# 06_Logic_Level_Shifters.net
KiCad netlist of a schematic drawn in Altium Designer
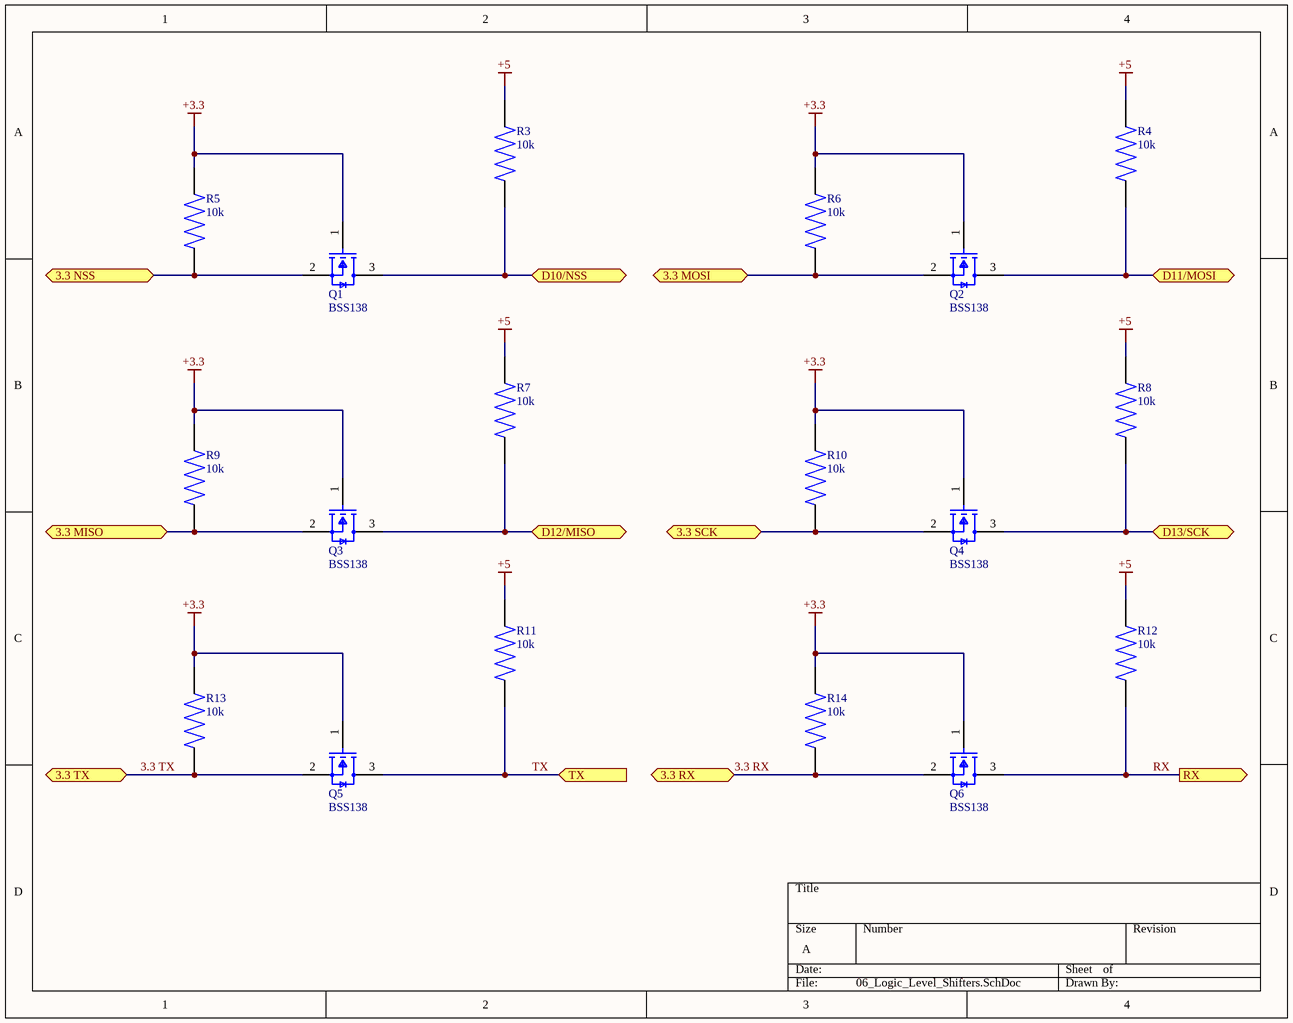
[diagram p0: 06_Logic_Level_Shifters.SchDoc]

(export (version "E")
  (design (tool "Eeschema 10.0.6"))
  (components
    (comp (ref "Q1")
      (value "BSS138")
      (footprint "FP-318-08-IPC_B")
      (description "MOSFET N-CH 50V 220MA SOT-23")
      (libsource (lib "Altium Content Vault") (part "3b9c635fedb024a5347a57b145af9cc"))
    )
    (comp (ref "Q2")
      (value "BSS138")
      (footprint "FP-318-08-IPC_B")
      (description "MOSFET N-CH 50V 220MA SOT-23")
      (libsource (lib "Altium Content Vault") (part "3b9c635fedb024a5347a57b145af9cc"))
    )
    (comp (ref "Q3")
      (value "BSS138")
      (footprint "FP-318-08-IPC_B")
      (description "MOSFET N-CH 50V 220MA SOT-23")
      (libsource (lib "Altium Content Vault") (part "3b9c635fedb024a5347a57b145af9cc"))
    )
    (comp (ref "Q4")
      (value "BSS138")
      (footprint "FP-318-08-IPC_B")
      (description "MOSFET N-CH 50V 220MA SOT-23")
      (libsource (lib "Altium Content Vault") (part "3b9c635fedb024a5347a57b145af9cc"))
    )
    (comp (ref "Q5")
      (value "BSS138")
      (footprint "FP-318-08-IPC_B")
      (description "MOSFET N-CH 50V 220MA SOT-23")
      (libsource (lib "Altium Content Vault") (part "3b9c635fedb024a5347a57b145af9cc"))
    )
    (comp (ref "Q6")
      (value "BSS138")
      (footprint "FP-318-08-IPC_B")
      (description "MOSFET N-CH 50V 220MA SOT-23")
      (libsource (lib "Altium Content Vault") (part "3b9c635fedb024a5347a57b145af9cc"))
    )
    (comp (ref "R3")
      (value "10k")
      (footprint "RESC3115X65N")
      (description "Res Thick Film 1206 4.7K Ohm 1% 0.25W(1/4W) Â±100ppm/C Pad SMD T/R")
      (fields (field (name "MF") "TE Connectivity") (field (name "MP") "CRG1206F4K7/10"))
      (libsource (lib "RFID") (part "CRG1206F4K7/10"))
    )
    (comp (ref "R4")
      (value "10k")
      (footprint "RESC3115X65N")
      (description "Res Thick Film 1206 4.7K Ohm 1% 0.25W(1/4W) Â±100ppm/C Pad SMD T/R")
      (fields (field (name "MF") "TE Connectivity") (field (name "MP") "CRG1206F4K7/10"))
      (libsource (lib "RFID") (part "CRG1206F4K7/10"))
    )
    (comp (ref "R5")
      (value "10k")
      (footprint "RESC3115X65N")
      (description "Res Thick Film 1206 4.7K Ohm 1% 0.25W(1/4W) Â±100ppm/C Pad SMD T/R")
      (fields (field (name "MF") "TE Connectivity") (field (name "MP") "CRG1206F4K7/10"))
      (libsource (lib "RFID") (part "CRG1206F4K7/10"))
    )
    (comp (ref "R6")
      (value "10k")
      (footprint "RESC3115X65N")
      (description "Res Thick Film 1206 4.7K Ohm 1% 0.25W(1/4W) Â±100ppm/C Pad SMD T/R")
      (fields (field (name "MF") "TE Connectivity") (field (name "MP") "CRG1206F4K7/10"))
      (libsource (lib "RFID") (part "CRG1206F4K7/10"))
    )
    (comp (ref "R7")
      (value "10k")
      (footprint "RESC3115X65N")
      (description "Res Thick Film 1206 4.7K Ohm 1% 0.25W(1/4W) Â±100ppm/C Pad SMD T/R")
      (fields (field (name "MF") "TE Connectivity") (field (name "MP") "CRG1206F4K7/10"))
      (libsource (lib "RFID") (part "CRG1206F4K7/10"))
    )
    (comp (ref "R8")
      (value "10k")
      (footprint "RESC3115X65N")
      (description "Res Thick Film 1206 4.7K Ohm 1% 0.25W(1/4W) Â±100ppm/C Pad SMD T/R")
      (fields (field (name "MF") "TE Connectivity") (field (name "MP") "CRG1206F4K7/10"))
      (libsource (lib "RFID") (part "CRG1206F4K7/10"))
    )
    (comp (ref "R9")
      (value "10k")
      (footprint "RESC3115X65N")
      (description "Res Thick Film 1206 4.7K Ohm 1% 0.25W(1/4W) Â±100ppm/C Pad SMD T/R")
      (fields (field (name "MF") "TE Connectivity") (field (name "MP") "CRG1206F4K7/10"))
      (libsource (lib "RFID") (part "CRG1206F4K7/10"))
    )
    (comp (ref "R10")
      (value "10k")
      (footprint "RESC3115X65N")
      (description "Res Thick Film 1206 4.7K Ohm 1% 0.25W(1/4W) Â±100ppm/C Pad SMD T/R")
      (fields (field (name "MF") "TE Connectivity") (field (name "MP") "CRG1206F4K7/10"))
      (libsource (lib "RFID") (part "CRG1206F4K7/10"))
    )
    (comp (ref "R11")
      (value "10k")
      (footprint "RESC3115X65N")
      (description "Res Thick Film 1206 4.7K Ohm 1% 0.25W(1/4W) Â±100ppm/C Pad SMD T/R")
      (fields (field (name "MF") "TE Connectivity") (field (name "MP") "CRG1206F4K7/10"))
      (libsource (lib "RFID") (part "CRG1206F4K7/10"))
    )
    (comp (ref "R12")
      (value "10k")
      (footprint "RESC3115X65N")
      (description "Res Thick Film 1206 4.7K Ohm 1% 0.25W(1/4W) Â±100ppm/C Pad SMD T/R")
      (fields (field (name "MF") "TE Connectivity") (field (name "MP") "CRG1206F4K7/10"))
      (libsource (lib "RFID") (part "CRG1206F4K7/10"))
    )
    (comp (ref "R13")
      (value "10k")
      (footprint "RESC3115X65N")
      (description "Res Thick Film 1206 4.7K Ohm 1% 0.25W(1/4W) Â±100ppm/C Pad SMD T/R")
      (fields (field (name "MF") "TE Connectivity") (field (name "MP") "CRG1206F4K7/10"))
      (libsource (lib "RFID") (part "CRG1206F4K7/10"))
    )
    (comp (ref "R14")
      (value "10k")
      (footprint "RESC3115X65N")
      (description "Res Thick Film 1206 4.7K Ohm 1% 0.25W(1/4W) Â±100ppm/C Pad SMD T/R")
      (fields (field (name "MF") "TE Connectivity") (field (name "MP") "CRG1206F4K7/10"))
      (libsource (lib "RFID") (part "CRG1206F4K7/10"))
    )
  )
  (nets
    (net (code "1") (name "+3.3") (class "Default")
      (node (ref "Q1") (pin "1") (pinfunction "G_1") (pintype "passive"))
      (node (ref "Q2") (pin "1") (pinfunction "G_1") (pintype "passive"))
      (node (ref "Q3") (pin "1") (pinfunction "G_1") (pintype "passive"))
      (node (ref "Q4") (pin "1") (pinfunction "G_1") (pintype "passive"))
      (node (ref "Q5") (pin "1") (pinfunction "G_1") (pintype "passive"))
      (node (ref "Q6") (pin "1") (pinfunction "G_1") (pintype "passive"))
      (node (ref "R10") (pin "2") (pinfunction "2_2") (pintype "passive"))
      (node (ref "R13") (pin "2") (pinfunction "2_2") (pintype "passive"))
      (node (ref "R14") (pin "2") (pinfunction "2_2") (pintype "passive"))
      (node (ref "R5") (pin "2") (pinfunction "2_2") (pintype "passive"))
      (node (ref "R6") (pin "2") (pinfunction "2_2") (pintype "passive"))
      (node (ref "R9") (pin "2") (pinfunction "2_2") (pintype "passive"))
    )
    (net (code "2") (name "+5") (class "Default")
      (node (ref "R11") (pin "2") (pinfunction "2_2") (pintype "passive"))
      (node (ref "R12") (pin "2") (pinfunction "2_2") (pintype "passive"))
      (node (ref "R3") (pin "2") (pinfunction "2_2") (pintype "passive"))
      (node (ref "R4") (pin "2") (pinfunction "2_2") (pintype "passive"))
      (node (ref "R7") (pin "2") (pinfunction "2_2") (pintype "passive"))
      (node (ref "R8") (pin "2") (pinfunction "2_2") (pintype "passive"))
    )
    (net (code "3") (name "/3.3 MISO") (class "Default")
      (node (ref "Q3") (pin "2") (pinfunction "S_2") (pintype "passive"))
      (node (ref "R9") (pin "1") (pinfunction "1_1") (pintype "passive"))
    )
    (net (code "4") (name "/3.3 MOSI") (class "Default")
      (node (ref "Q2") (pin "2") (pinfunction "S_2") (pintype "passive"))
      (node (ref "R6") (pin "1") (pinfunction "1_1") (pintype "passive"))
    )
    (net (code "5") (name "/3.3 NSS") (class "Default")
      (node (ref "Q1") (pin "2") (pinfunction "S_2") (pintype "passive"))
      (node (ref "R5") (pin "1") (pinfunction "1_1") (pintype "passive"))
    )
    (net (code "6") (name "/3.3 RX") (class "Default")
      (node (ref "Q6") (pin "2") (pinfunction "S_2") (pintype "passive"))
      (node (ref "R14") (pin "1") (pinfunction "1_1") (pintype "passive"))
    )
    (net (code "7") (name "/3.3 SCK") (class "Default")
      (node (ref "Q4") (pin "2") (pinfunction "S_2") (pintype "passive"))
      (node (ref "R10") (pin "1") (pinfunction "1_1") (pintype "passive"))
    )
    (net (code "8") (name "/3.3 TX") (class "Default")
      (node (ref "Q5") (pin "2") (pinfunction "S_2") (pintype "passive"))
      (node (ref "R13") (pin "1") (pinfunction "1_1") (pintype "passive"))
    )
    (net (code "9") (name "/D10{slash}NSS") (class "Default")
      (node (ref "Q1") (pin "3") (pinfunction "D_3") (pintype "passive"))
      (node (ref "R3") (pin "1") (pinfunction "1_1") (pintype "passive"))
    )
    (net (code "10") (name "/D11{slash}MOSI") (class "Default")
      (node (ref "Q2") (pin "3") (pinfunction "D_3") (pintype "passive"))
      (node (ref "R4") (pin "1") (pinfunction "1_1") (pintype "passive"))
    )
    (net (code "11") (name "/D12{slash}MISO") (class "Default")
      (node (ref "Q3") (pin "3") (pinfunction "D_3") (pintype "passive"))
      (node (ref "R7") (pin "1") (pinfunction "1_1") (pintype "passive"))
    )
    (net (code "12") (name "/D13{slash}SCK") (class "Default")
      (node (ref "Q4") (pin "3") (pinfunction "D_3") (pintype "passive"))
      (node (ref "R8") (pin "1") (pinfunction "1_1") (pintype "passive"))
    )
    (net (code "13") (name "/RX") (class "Default")
      (node (ref "Q6") (pin "3") (pinfunction "D_3") (pintype "passive"))
      (node (ref "R12") (pin "1") (pinfunction "1_1") (pintype "passive"))
    )
    (net (code "14") (name "/TX") (class "Default")
      (node (ref "Q5") (pin "3") (pinfunction "D_3") (pintype "passive"))
      (node (ref "R11") (pin "1") (pinfunction "1_1") (pintype "passive"))
    )
  )
)
